# max21100.net
KiCad netlist of a schematic drawn in EAGLE
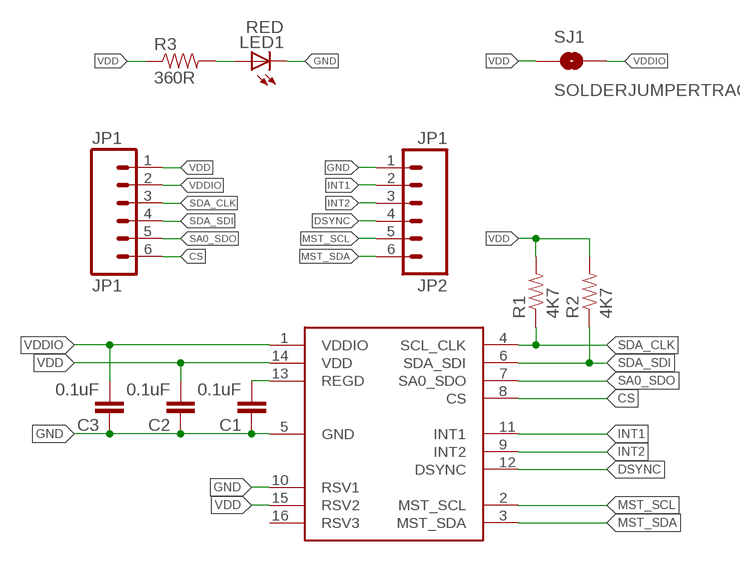
[diagram p0: schematic, sheet 1]

(export (version "E")
  (design (tool "Eeschema 10.0.6"))
  (components
    (comp (ref "C1")
      (value "0.1uF")
      (footprint "eagle-import:0603-CAP")
      (libsource (lib "eagle-import") (part "CAP0603-CAP"))
    )
    (comp (ref "C2")
      (value "0.1uF")
      (footprint "eagle-import:0603-CAP")
      (libsource (lib "eagle-import") (part "CAP0603-CAP"))
    )
    (comp (ref "C3")
      (value "0.1uF")
      (footprint "eagle-import:0603-CAP")
      (libsource (lib "eagle-import") (part "CAP0603-CAP"))
    )
    (comp (ref "JP1")
      (value "JP1")
      (footprint "eagle-import:1X06")
      (libsource (lib "eagle-import") (part "M06SIP"))
    )
    (comp (ref "JP2")
      (value "JP1")
      (footprint "eagle-import:1X06")
      (libsource (lib "eagle-import") (part "M06SIP"))
    )
    (comp (ref "LED1")
      (value "RED")
      (footprint "eagle-import:CHIP-LED0603")
      (libsource (lib "eagle-import") (part "LEDCHIP-LED0603"))
    )
    (comp (ref "R1")
      (value "4K7")
      (footprint "eagle-import:0603-RES")
      (libsource (lib "eagle-import") (part "RESISTOR0603-RES"))
    )
    (comp (ref "R2")
      (value "4K7")
      (footprint "eagle-import:0603-RES")
      (libsource (lib "eagle-import") (part "RESISTOR0603-RES"))
    )
    (comp (ref "R3")
      (value "360R")
      (footprint "eagle-import:0603-RES")
      (libsource (lib "eagle-import") (part "RESISTOR0603-RES"))
    )
    (comp (ref "SJ1")
      (value "SOLDERJUMPERTRACE")
      (footprint "eagle-import:SJ_2S-TRACE")
      (libsource (lib "eagle-import") (part "SOLDERJUMPERTRACE"))
    )
    (comp (ref "U$1")
      (value "MAX21100")
      (footprint "eagle-import:MAX21100")
      (libsource (lib "eagle-import") (part "MAX21100"))
    )
  )
  (nets
    (net (code "1") (name "CS") (class "Default")
      (node (ref "JP1") (pin "6") (pinfunction "6_6") (pintype "passive"))
      (node (ref "U$1") (pin "8") (pinfunction "CS_8") (pintype "bidirectional"))
    )
    (net (code "2") (name "DSYNC") (class "Default")
      (node (ref "JP2") (pin "4") (pinfunction "4_4") (pintype "passive"))
      (node (ref "U$1") (pin "12") (pinfunction "DSYNC_12") (pintype "bidirectional"))
    )
    (net (code "3") (name "GND") (class "Default")
      (node (ref "C1") (pin "1") (pinfunction "1_1") (pintype "passive"))
      (node (ref "C2") (pin "1") (pinfunction "1_1") (pintype "passive"))
      (node (ref "C3") (pin "1") (pinfunction "1_1") (pintype "passive"))
      (node (ref "JP2") (pin "1") (pinfunction "1_1") (pintype "passive"))
      (node (ref "LED1") (pin "C") (pinfunction "C_C") (pintype "passive"))
      (node (ref "U$1") (pin "10") (pinfunction "RSV1_10") (pintype "bidirectional"))
      (node (ref "U$1") (pin "5") (pinfunction "GND_5") (pintype "bidirectional"))
    )
    (net (code "4") (name "INT1") (class "Default")
      (node (ref "JP2") (pin "2") (pinfunction "2_2") (pintype "passive"))
      (node (ref "U$1") (pin "11") (pinfunction "INT1_11") (pintype "bidirectional"))
    )
    (net (code "5") (name "INT2") (class "Default")
      (node (ref "JP2") (pin "3") (pinfunction "3_3") (pintype "passive"))
      (node (ref "U$1") (pin "9") (pinfunction "INT2_9") (pintype "bidirectional"))
    )
    (net (code "6") (name "MST_SCL") (class "Default")
      (node (ref "JP2") (pin "5") (pinfunction "5_5") (pintype "passive"))
      (node (ref "U$1") (pin "2") (pinfunction "MST_SCL_2") (pintype "bidirectional"))
    )
    (net (code "7") (name "MST_SDA") (class "Default")
      (node (ref "JP2") (pin "6") (pinfunction "6_6") (pintype "passive"))
      (node (ref "U$1") (pin "3") (pinfunction "MST_SDA_3") (pintype "bidirectional"))
    )
    (net (code "8") (name "Net-(LED1-PadA)") (class "Default")
      (node (ref "LED1") (pin "A") (pinfunction "A_A") (pintype "passive"))
      (node (ref "R3") (pin "2") (pinfunction "2_2") (pintype "passive"))
    )
    (net (code "9") (name "Net-(U$1-REGD)") (class "Default")
      (node (ref "C1") (pin "2") (pinfunction "2_2") (pintype "passive"))
      (node (ref "U$1") (pin "13") (pinfunction "REGD_13") (pintype "bidirectional"))
    )
    (net (code "10") (name "SA0_SDO") (class "Default")
      (node (ref "JP1") (pin "5") (pinfunction "5_5") (pintype "passive"))
      (node (ref "U$1") (pin "7") (pinfunction "SA0_SDO_7") (pintype "bidirectional"))
    )
    (net (code "11") (name "SDA_CLK") (class "Default")
      (node (ref "JP1") (pin "3") (pinfunction "3_3") (pintype "passive"))
      (node (ref "R1") (pin "1") (pinfunction "1_1") (pintype "passive"))
      (node (ref "U$1") (pin "4") (pinfunction "SCL_CLK_4") (pintype "bidirectional"))
    )
    (net (code "12") (name "SDA_SDI") (class "Default")
      (node (ref "JP1") (pin "4") (pinfunction "4_4") (pintype "passive"))
      (node (ref "R2") (pin "1") (pinfunction "1_1") (pintype "passive"))
      (node (ref "U$1") (pin "6") (pinfunction "SDA_SDI_6") (pintype "bidirectional"))
    )
    (net (code "13") (name "VDD") (class "Default")
      (node (ref "C2") (pin "2") (pinfunction "2_2") (pintype "passive"))
      (node (ref "JP1") (pin "1") (pinfunction "1_1") (pintype "passive"))
      (node (ref "R1") (pin "2") (pinfunction "2_2") (pintype "passive"))
      (node (ref "R2") (pin "2") (pinfunction "2_2") (pintype "passive"))
      (node (ref "R3") (pin "1") (pinfunction "1_1") (pintype "passive"))
      (node (ref "SJ1") (pin "1") (pinfunction "1_1") (pintype "passive"))
      (node (ref "U$1") (pin "14") (pinfunction "VDD_14") (pintype "bidirectional"))
      (node (ref "U$1") (pin "15") (pinfunction "RSV2_15") (pintype "bidirectional"))
    )
    (net (code "14") (name "VDDIO") (class "Default")
      (node (ref "C3") (pin "2") (pinfunction "2_2") (pintype "passive"))
      (node (ref "JP1") (pin "2") (pinfunction "2_2") (pintype "passive"))
      (node (ref "SJ1") (pin "2") (pinfunction "2_2") (pintype "passive"))
      (node (ref "U$1") (pin "1") (pinfunction "VDDIO_1") (pintype "bidirectional"))
    )
    (net (code "15") (name "unconnected-(U$1-RSV3-Pad16)") (class "Default")
      (node (ref "U$1") (pin "16") (pinfunction "RSV3_16") (pintype "bidirectional"))
    )
  )
)
